# v2.net
KiCad netlist of a schematic drawn in EAGLE
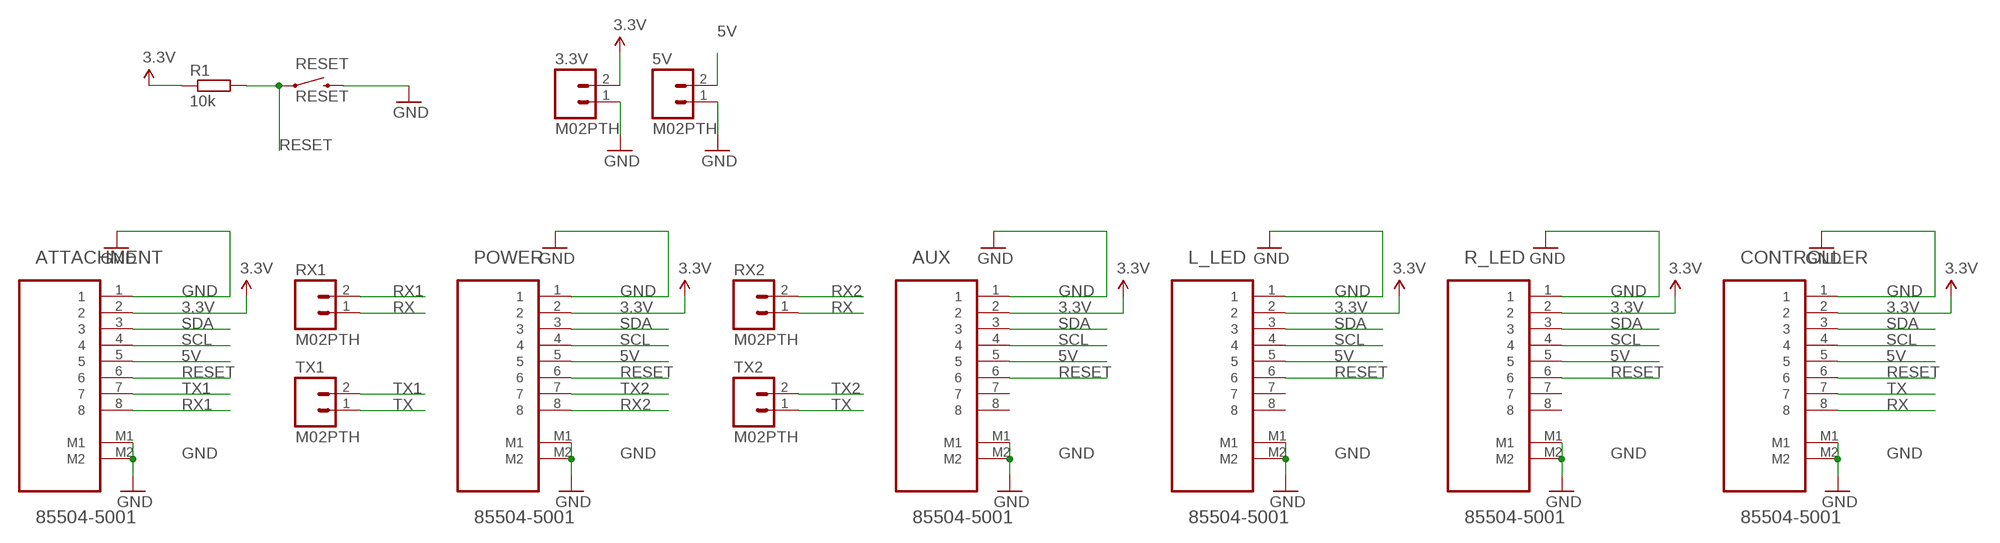
[diagram p0: schematic, sheet 1]

(export (version "E")
  (design (tool "Eeschema 10.0.6"))
  (components
    (comp (ref "3.3V")
      (value "M02PTH")
      (footprint "eagle-import:1X02")
      (libsource (lib "eagle-import") (part "M02PTH"))
    )
    (comp (ref "5V")
      (value "M02PTH")
      (footprint "eagle-import:1X02")
      (libsource (lib "eagle-import") (part "M02PTH"))
    )
    (comp (ref "ATTACHMENT")
      (value "85504-5001")
      (footprint "eagle-import:MOLEX_85504-5001")
      (libsource (lib "eagle-import") (part "85504-5001"))
    )
    (comp (ref "AUX")
      (value "85504-5001")
      (footprint "eagle-import:MOLEX_85504-5001")
      (libsource (lib "eagle-import") (part "85504-5001"))
    )
    (comp (ref "CONTROLLER")
      (value "85504-5001")
      (footprint "eagle-import:MOLEX_85504-5001")
      (libsource (lib "eagle-import") (part "85504-5001"))
    )
    (comp (ref "L_LED")
      (value "85504-5001")
      (footprint "eagle-import:MOLEX_85504-5001")
      (libsource (lib "eagle-import") (part "85504-5001"))
    )
    (comp (ref "POWER")
      (value "85504-5001")
      (footprint "eagle-import:MOLEX_85504-5001")
      (libsource (lib "eagle-import") (part "85504-5001"))
    )
    (comp (ref "R1")
      (value "10k")
      (footprint "eagle-import:R0805")
      (libsource (lib "eagle-import") (part "R-EU_R0805"))
    )
    (comp (ref "RESET")
      (value "RESET")
      (footprint "eagle-import:TACTILE-PTH")
      (libsource (lib "eagle-import") (part "SWITCH-MOMENTARY-2PTH"))
    )
    (comp (ref "RX1")
      (value "M02PTH")
      (footprint "eagle-import:1X02")
      (libsource (lib "eagle-import") (part "M02PTH"))
    )
    (comp (ref "RX2")
      (value "M02PTH")
      (footprint "eagle-import:1X02")
      (libsource (lib "eagle-import") (part "M02PTH"))
    )
    (comp (ref "R_LED")
      (value "85504-5001")
      (footprint "eagle-import:MOLEX_85504-5001")
      (libsource (lib "eagle-import") (part "85504-5001"))
    )
    (comp (ref "TX1")
      (value "M02PTH")
      (footprint "eagle-import:1X02")
      (libsource (lib "eagle-import") (part "M02PTH"))
    )
    (comp (ref "TX2")
      (value "M02PTH")
      (footprint "eagle-import:1X02")
      (libsource (lib "eagle-import") (part "M02PTH"))
    )
  )
  (nets
    (net (code "1") (name "/5V") (class "Default")
      (node (ref "5V") (pin "2") (pinfunction "2_2") (pintype "passive"))
      (node (ref "ATTACHMENT") (pin "5") (pinfunction "5_5") (pintype "bidirectional"))
      (node (ref "AUX") (pin "5") (pinfunction "5_5") (pintype "bidirectional"))
      (node (ref "CONTROLLER") (pin "5") (pinfunction "5_5") (pintype "bidirectional"))
      (node (ref "L_LED") (pin "5") (pinfunction "5_5") (pintype "bidirectional"))
      (node (ref "POWER") (pin "5") (pinfunction "5_5") (pintype "bidirectional"))
      (node (ref "R_LED") (pin "5") (pinfunction "5_5") (pintype "bidirectional"))
    )
    (net (code "2") (name "/RESET") (class "Default")
      (node (ref "ATTACHMENT") (pin "6") (pinfunction "6_6") (pintype "bidirectional"))
      (node (ref "AUX") (pin "6") (pinfunction "6_6") (pintype "bidirectional"))
      (node (ref "CONTROLLER") (pin "6") (pinfunction "6_6") (pintype "bidirectional"))
      (node (ref "L_LED") (pin "6") (pinfunction "6_6") (pintype "bidirectional"))
      (node (ref "POWER") (pin "6") (pinfunction "6_6") (pintype "bidirectional"))
      (node (ref "R1") (pin "2") (pinfunction "2_2") (pintype "passive"))
      (node (ref "RESET") (pin "1") (pinfunction "1_1") (pintype "passive"))
      (node (ref "R_LED") (pin "6") (pinfunction "6_6") (pintype "bidirectional"))
    )
    (net (code "3") (name "/RX") (class "Default")
      (node (ref "CONTROLLER") (pin "8") (pinfunction "8_8") (pintype "bidirectional"))
      (node (ref "RX1") (pin "1") (pinfunction "1_1") (pintype "passive"))
      (node (ref "RX2") (pin "1") (pinfunction "1_1") (pintype "passive"))
    )
    (net (code "4") (name "/RX1") (class "Default")
      (node (ref "ATTACHMENT") (pin "8") (pinfunction "8_8") (pintype "bidirectional"))
      (node (ref "RX1") (pin "2") (pinfunction "2_2") (pintype "passive"))
    )
    (net (code "5") (name "/RX2") (class "Default")
      (node (ref "POWER") (pin "8") (pinfunction "8_8") (pintype "bidirectional"))
      (node (ref "RX2") (pin "2") (pinfunction "2_2") (pintype "passive"))
    )
    (net (code "6") (name "/SCL") (class "Default")
      (node (ref "ATTACHMENT") (pin "4") (pinfunction "4_4") (pintype "bidirectional"))
      (node (ref "AUX") (pin "4") (pinfunction "4_4") (pintype "bidirectional"))
      (node (ref "CONTROLLER") (pin "4") (pinfunction "4_4") (pintype "bidirectional"))
      (node (ref "L_LED") (pin "4") (pinfunction "4_4") (pintype "bidirectional"))
      (node (ref "POWER") (pin "4") (pinfunction "4_4") (pintype "bidirectional"))
      (node (ref "R_LED") (pin "4") (pinfunction "4_4") (pintype "bidirectional"))
    )
    (net (code "7") (name "/SDA") (class "Default")
      (node (ref "ATTACHMENT") (pin "3") (pinfunction "3_3") (pintype "bidirectional"))
      (node (ref "AUX") (pin "3") (pinfunction "3_3") (pintype "bidirectional"))
      (node (ref "CONTROLLER") (pin "3") (pinfunction "3_3") (pintype "bidirectional"))
      (node (ref "L_LED") (pin "3") (pinfunction "3_3") (pintype "bidirectional"))
      (node (ref "POWER") (pin "3") (pinfunction "3_3") (pintype "bidirectional"))
      (node (ref "R_LED") (pin "3") (pinfunction "3_3") (pintype "bidirectional"))
    )
    (net (code "8") (name "/TX") (class "Default")
      (node (ref "CONTROLLER") (pin "7") (pinfunction "7_7") (pintype "bidirectional"))
      (node (ref "TX1") (pin "1") (pinfunction "1_1") (pintype "passive"))
      (node (ref "TX2") (pin "1") (pinfunction "1_1") (pintype "passive"))
    )
    (net (code "9") (name "/TX1") (class "Default")
      (node (ref "ATTACHMENT") (pin "7") (pinfunction "7_7") (pintype "bidirectional"))
      (node (ref "TX1") (pin "2") (pinfunction "2_2") (pintype "passive"))
    )
    (net (code "10") (name "/TX2") (class "Default")
      (node (ref "POWER") (pin "7") (pinfunction "7_7") (pintype "bidirectional"))
      (node (ref "TX2") (pin "2") (pinfunction "2_2") (pintype "passive"))
    )
    (net (code "11") (name "3.3V") (class "Default")
      (node (ref "3.3V") (pin "2") (pinfunction "2_2") (pintype "passive"))
      (node (ref "ATTACHMENT") (pin "2") (pinfunction "2_2") (pintype "bidirectional"))
      (node (ref "AUX") (pin "2") (pinfunction "2_2") (pintype "bidirectional"))
      (node (ref "CONTROLLER") (pin "2") (pinfunction "2_2") (pintype "bidirectional"))
      (node (ref "L_LED") (pin "2") (pinfunction "2_2") (pintype "bidirectional"))
      (node (ref "POWER") (pin "2") (pinfunction "2_2") (pintype "bidirectional"))
      (node (ref "R1") (pin "1") (pinfunction "1_1") (pintype "passive"))
      (node (ref "R_LED") (pin "2") (pinfunction "2_2") (pintype "bidirectional"))
    )
    (net (code "12") (name "GND") (class "Default")
      (node (ref "3.3V") (pin "1") (pinfunction "1_1") (pintype "passive"))
      (node (ref "5V") (pin "1") (pinfunction "1_1") (pintype "passive"))
      (node (ref "ATTACHMENT") (pin "1") (pinfunction "1_1") (pintype "bidirectional"))
      (node (ref "ATTACHMENT") (pin "M1") (pinfunction "M1_M1") (pintype "bidirectional"))
      (node (ref "ATTACHMENT") (pin "M2") (pinfunction "M2_M2") (pintype "bidirectional"))
      (node (ref "AUX") (pin "1") (pinfunction "1_1") (pintype "bidirectional"))
      (node (ref "AUX") (pin "M1") (pinfunction "M1_M1") (pintype "bidirectional"))
      (node (ref "AUX") (pin "M2") (pinfunction "M2_M2") (pintype "bidirectional"))
      (node (ref "CONTROLLER") (pin "1") (pinfunction "1_1") (pintype "bidirectional"))
      (node (ref "CONTROLLER") (pin "M1") (pinfunction "M1_M1") (pintype "bidirectional"))
      (node (ref "CONTROLLER") (pin "M2") (pinfunction "M2_M2") (pintype "bidirectional"))
      (node (ref "L_LED") (pin "1") (pinfunction "1_1") (pintype "bidirectional"))
      (node (ref "L_LED") (pin "M1") (pinfunction "M1_M1") (pintype "bidirectional"))
      (node (ref "L_LED") (pin "M2") (pinfunction "M2_M2") (pintype "bidirectional"))
      (node (ref "POWER") (pin "1") (pinfunction "1_1") (pintype "bidirectional"))
      (node (ref "POWER") (pin "M1") (pinfunction "M1_M1") (pintype "bidirectional"))
      (node (ref "POWER") (pin "M2") (pinfunction "M2_M2") (pintype "bidirectional"))
      (node (ref "RESET") (pin "3") (pinfunction "2_3") (pintype "passive"))
      (node (ref "R_LED") (pin "1") (pinfunction "1_1") (pintype "bidirectional"))
      (node (ref "R_LED") (pin "M1") (pinfunction "M1_M1") (pintype "bidirectional"))
      (node (ref "R_LED") (pin "M2") (pinfunction "M2_M2") (pintype "bidirectional"))
    )
    (net (code "13") (name "unconnected-(AUX-Pad7)") (class "Default")
      (node (ref "AUX") (pin "7") (pinfunction "7_7") (pintype "bidirectional"))
    )
    (net (code "14") (name "unconnected-(AUX-Pad8)") (class "Default")
      (node (ref "AUX") (pin "8") (pinfunction "8_8") (pintype "bidirectional"))
    )
    (net (code "15") (name "unconnected-(L_LED-Pad7)") (class "Default")
      (node (ref "L_LED") (pin "7") (pinfunction "7_7") (pintype "bidirectional"))
    )
    (net (code "16") (name "unconnected-(L_LED-Pad8)") (class "Default")
      (node (ref "L_LED") (pin "8") (pinfunction "8_8") (pintype "bidirectional"))
    )
    (net (code "17") (name "unconnected-(R_LED-Pad7)") (class "Default")
      (node (ref "R_LED") (pin "7") (pinfunction "7_7") (pintype "bidirectional"))
    )
    (net (code "18") (name "unconnected-(R_LED-Pad8)") (class "Default")
      (node (ref "R_LED") (pin "8") (pinfunction "8_8") (pintype "bidirectional"))
    )
  )
)
